# Volant5_ROTARY_SW_v1_0.net
KiCad netlist of a schematic drawn in Altium Designer
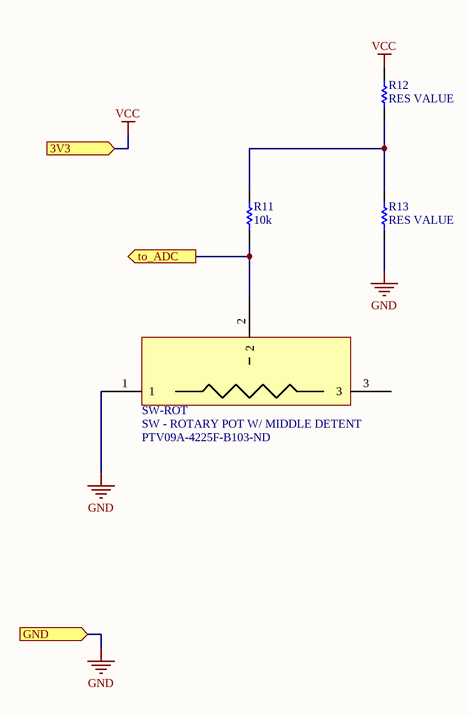
[diagram p0: Volant5.ROTARY_SW_v1.0.SchDoc]

(export (version "E")
  (design (tool "Eeschema 10.0.6"))
  (components
    (comp (ref "R11")
      (value "10k")
      (footprint "RS-0603")
      (fields
        (field (name "TOLERANCE") "RES TOL")
        (field (name "POWER") "RES POWER")
        (field (name "Comment") "RS - RESISTOR")
      )
      (libsource (lib "CHINOOK_LIBRARY") (part "RS - RESISTOR"))
    )
    (comp (ref "R12")
      (value "RES VALUE")
      (footprint "RS-0603")
      (fields
        (field (name "TOLERANCE") "RES TOL")
        (field (name "POWER") "RES POWER")
        (field (name "Comment") "RS - RESISTOR")
      )
      (libsource (lib "CHINOOK_LIBRARY") (part "RS - RESISTOR"))
    )
    (comp (ref "R13")
      (value "RES VALUE")
      (footprint "RS-0603")
      (fields
        (field (name "TOLERANCE") "RES TOL")
        (field (name "POWER") "RES POWER")
        (field (name "Comment") "RS - RESISTOR")
      )
      (libsource (lib "CHINOOK_LIBRARY") (part "RS - RESISTOR"))
    )
    (comp (ref "SW-ROT")
      (value "SW - ROTARY POT W/ MIDDLE DETENT")
      (footprint "SW - ROTARY POT W/ DETENT")
      (description "Potentiomètre rotatif +-140 deg avec détente au milieu")
      (fields (field (name "SUPPLIER PART NUMBER 1") "PTV09A-4225F-B103-ND"))
      (libsource (lib "CHINOOK_LIBRARY") (part "SW - ROTARY POT W/ MIDDLE DETENT"))
    )
  )
  (nets
    (net (code "1") (name "/to_ADC") (class "Default")
      (node (ref "R11") (pin "1") (pinfunction "1_1") (pintype "passive"))
      (node (ref "SW-ROT") (pin "2") (pinfunction "2_2") (pintype "passive"))
    )
    (net (code "2") (name "GND") (class "Default")
      (node (ref "R13") (pin "1") (pinfunction "1_1") (pintype "passive"))
      (node (ref "SW-ROT") (pin "1") (pinfunction "1_1") (pintype "passive"))
    )
    (net (code "3") (name "Net-(R11-Pad2)") (class "Default")
      (node (ref "R11") (pin "2") (pinfunction "2_2") (pintype "passive"))
      (node (ref "R12") (pin "1") (pinfunction "1_1") (pintype "passive"))
      (node (ref "R13") (pin "2") (pinfunction "2_2") (pintype "passive"))
    )
    (net (code "4") (name "VCC") (class "Default")
      (node (ref "R12") (pin "2") (pinfunction "2_2") (pintype "passive"))
    )
    (net (code "5") (name "unconnected-(SW-ROT-Pad3)") (class "Default")
      (node (ref "SW-ROT") (pin "3") (pinfunction "3_3") (pintype "passive"))
    )
  )
)
